# H3AR00.net
KiCad netlist of a schematic drawn in EAGLE
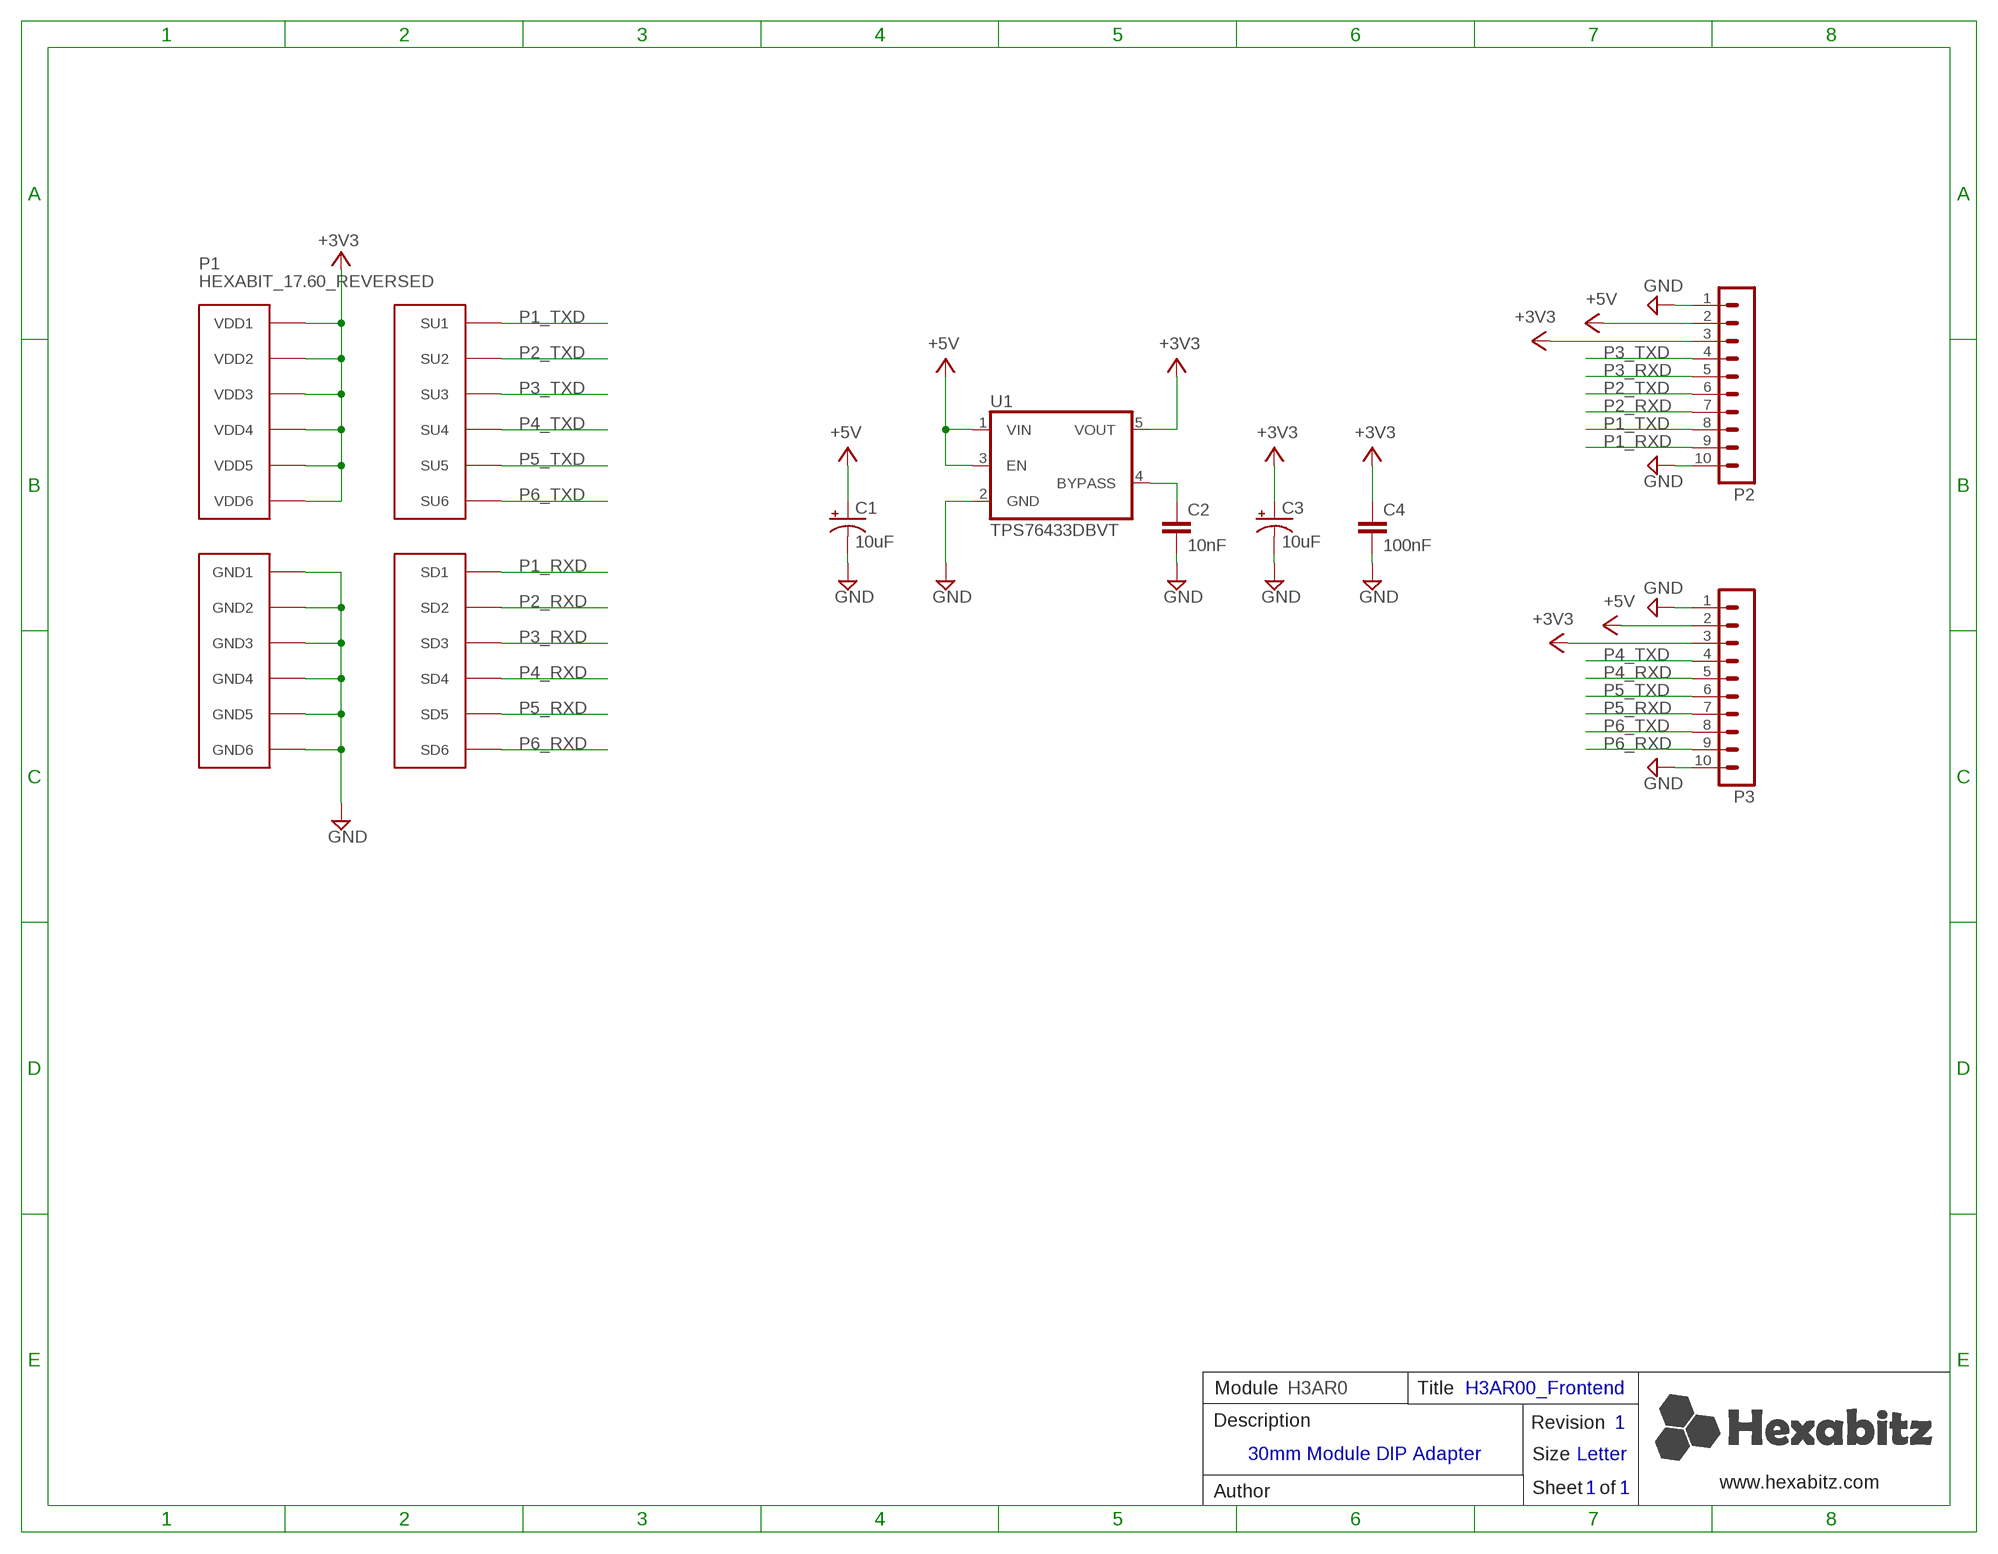
[diagram p0: schematic, sheet 1]

(export (version "E")
  (design (tool "Eeschema 10.0.6"))
  (components
    (comp (ref "C1")
      (value "10uF")
      (footprint "eagle-import:C-1210-POL")
      (fields
        (field (name "CAPACITANCE") "10uF")
        (field (name "MFN") "AVX")
        (field (name "MPN") "TPSB106K016R0500")
        (field (name "OCTOPART_URL") "https://octopart.com/tpsb106k016r0500-avx-1436890?r=sp#")
      )
      (libsource (lib "eagle-import") (part "C-1210-POL"))
    )
    (comp (ref "C2")
      (value "10nF")
      (footprint "eagle-import:C-0603")
      (fields
        (field (name "CAPACITANCE") "10nF")
        (field (name "MFN") "KEMET")
        (field (name "MPN") "C0603C103K5RACTU")
        (field (name "OCTOPART_URL") "https://octopart.com/c0603c103k5ractu-kemet-133094?r=sp&s=R_iPBxLnSmGqhkU2rIMFpg")
        (field (name "TOLERANCE") "10%")
        (field (name "VOLTAGE_RATING") "50V")
      )
      (libsource (lib "eagle-import") (part "C-0603"))
    )
    (comp (ref "C3")
      (value "10uF")
      (footprint "eagle-import:C-1210-POL")
      (fields
        (field (name "CAPACITANCE") "10uF")
        (field (name "MFN") "AVX")
        (field (name "MPN") "TPSB106K016R0500")
        (field (name "OCTOPART_URL") "https://octopart.com/tpsb106k016r0500-avx-1436890?r=sp#")
      )
      (libsource (lib "eagle-import") (part "C-1210-POL"))
    )
    (comp (ref "C4")
      (value "100nF")
      (footprint "eagle-import:C-0603")
      (fields
        (field (name "CAPACITANCE") "100nF")
        (field (name "MFN") "KEMET")
        (field (name "MPN") "C0603C104K8RACTU")
        (field (name "OCTOPART_URL") "https://octopart.com/c0603c104k8ractu-kemet-145075?r=sp&s=9bS9ASSwSEqMCE9KBEQZ0g")
        (field (name "TOLERANCE") "10%")
        (field (name "VOLTAGE_RATING") "10V")
      )
      (libsource (lib "eagle-import") (part "C-0603"))
    )
    (comp (ref "P1")
      (value "HEXABIT_17.60_REVERSED")
      (footprint "eagle-import:HEXABIT_17.60_REVERSED")
      (libsource (lib "eagle-import") (part "HEXABIT_?_REVERSED17.60"))
    )
    (comp (ref "P2")
      (value "MA10-1")
      (footprint "eagle-import:MA10-1")
      (fields (field (name "MPN") "61301011121"))
      (libsource (lib "eagle-import") (part "MA10-1"))
    )
    (comp (ref "P3")
      (value "MA10-1")
      (footprint "eagle-import:MA10-1")
      (fields (field (name "MPN") "61301011121"))
      (libsource (lib "eagle-import") (part "MA10-1"))
    )
    (comp (ref "U1")
      (value "TPS76433DBVT")
      (footprint "eagle-import:SOT25")
      (libsource (lib "eagle-import") (part "TPS764DBVT33"))
    )
  )
  (nets
    (net (code "1") (name "+3V3") (class "Default")
      (node (ref "C3") (pin "1") (pinfunction "+_1") (pintype "passive"))
      (node (ref "C4") (pin "1") (pinfunction "1_1") (pintype "passive"))
      (node (ref "P1") (pin "PAD_PU10") (pinfunction "VDD4_PAD_PU10") (pintype "power_in"))
      (node (ref "P1") (pin "PAD_PU11") (pinfunction "VDD5_PAD_PU11") (pintype "power_in"))
      (node (ref "P1") (pin "PAD_PU12") (pinfunction "VDD6_PAD_PU12") (pintype "power_in"))
      (node (ref "P1") (pin "PAD_PU7") (pinfunction "VDD1_PAD_PU7") (pintype "power_in"))
      (node (ref "P1") (pin "PAD_PU8") (pinfunction "VDD2_PAD_PU8") (pintype "power_in"))
      (node (ref "P1") (pin "PAD_PU9") (pinfunction "VDD3_PAD_PU9") (pintype "power_in"))
      (node (ref "P2") (pin "3") (pinfunction "3_3") (pintype "passive"))
      (node (ref "P3") (pin "3") (pinfunction "3_3") (pintype "passive"))
      (node (ref "U1") (pin "5") (pinfunction "VOUT_5") (pintype "passive"))
    )
    (net (code "2") (name "+5V") (class "Default")
      (node (ref "C1") (pin "1") (pinfunction "+_1") (pintype "passive"))
      (node (ref "P2") (pin "2") (pinfunction "2_2") (pintype "passive"))
      (node (ref "P3") (pin "2") (pinfunction "2_2") (pintype "passive"))
      (node (ref "U1") (pin "1") (pinfunction "VIN_1") (pintype "input"))
      (node (ref "U1") (pin "3") (pinfunction "EN_3") (pintype "input"))
    )
    (net (code "3") (name "/P1_RXD") (class "Default")
      (node (ref "P1") (pin "PAD_PD1") (pinfunction "SD1_PAD_PD1") (pintype "bidirectional"))
      (node (ref "P2") (pin "9") (pinfunction "9_9") (pintype "passive"))
    )
    (net (code "4") (name "/P1_TXD") (class "Default")
      (node (ref "P1") (pin "PAD_PU1") (pinfunction "SU1_PAD_PU1") (pintype "bidirectional"))
      (node (ref "P2") (pin "8") (pinfunction "8_8") (pintype "passive"))
    )
    (net (code "5") (name "/P2_RXD") (class "Default")
      (node (ref "P1") (pin "PAD_PD2") (pinfunction "SD2_PAD_PD2") (pintype "bidirectional"))
      (node (ref "P2") (pin "7") (pinfunction "7_7") (pintype "passive"))
    )
    (net (code "6") (name "/P2_TXD") (class "Default")
      (node (ref "P1") (pin "PAD_PU2") (pinfunction "SU2_PAD_PU2") (pintype "bidirectional"))
      (node (ref "P2") (pin "6") (pinfunction "6_6") (pintype "passive"))
    )
    (net (code "7") (name "/P3_RXD") (class "Default")
      (node (ref "P1") (pin "PAD_PD3") (pinfunction "SD3_PAD_PD3") (pintype "bidirectional"))
      (node (ref "P2") (pin "5") (pinfunction "5_5") (pintype "passive"))
    )
    (net (code "8") (name "/P3_TXD") (class "Default")
      (node (ref "P1") (pin "PAD_PU3") (pinfunction "SU3_PAD_PU3") (pintype "bidirectional"))
      (node (ref "P2") (pin "4") (pinfunction "4_4") (pintype "passive"))
    )
    (net (code "9") (name "/P4_RXD") (class "Default")
      (node (ref "P1") (pin "PAD_PD4") (pinfunction "SD4_PAD_PD4") (pintype "bidirectional"))
      (node (ref "P3") (pin "5") (pinfunction "5_5") (pintype "passive"))
    )
    (net (code "10") (name "/P4_TXD") (class "Default")
      (node (ref "P1") (pin "PAD_PU4") (pinfunction "SU4_PAD_PU4") (pintype "bidirectional"))
      (node (ref "P3") (pin "4") (pinfunction "4_4") (pintype "passive"))
    )
    (net (code "11") (name "/P5_RXD") (class "Default")
      (node (ref "P1") (pin "PAD_PD5") (pinfunction "SD5_PAD_PD5") (pintype "bidirectional"))
      (node (ref "P3") (pin "7") (pinfunction "7_7") (pintype "passive"))
    )
    (net (code "12") (name "/P5_TXD") (class "Default")
      (node (ref "P1") (pin "PAD_PU5") (pinfunction "SU5_PAD_PU5") (pintype "bidirectional"))
      (node (ref "P3") (pin "6") (pinfunction "6_6") (pintype "passive"))
    )
    (net (code "13") (name "/P6_RXD") (class "Default")
      (node (ref "P1") (pin "PAD_PD6") (pinfunction "SD6_PAD_PD6") (pintype "bidirectional"))
      (node (ref "P3") (pin "9") (pinfunction "9_9") (pintype "passive"))
    )
    (net (code "14") (name "/P6_TXD") (class "Default")
      (node (ref "P1") (pin "PAD_PU6") (pinfunction "SU6_PAD_PU6") (pintype "bidirectional"))
      (node (ref "P3") (pin "8") (pinfunction "8_8") (pintype "passive"))
    )
    (net (code "15") (name "GND") (class "Default")
      (node (ref "C1") (pin "2") (pinfunction "-_2") (pintype "passive"))
      (node (ref "C2") (pin "2") (pinfunction "2_2") (pintype "passive"))
      (node (ref "C3") (pin "2") (pinfunction "-_2") (pintype "passive"))
      (node (ref "C4") (pin "2") (pinfunction "2_2") (pintype "passive"))
      (node (ref "P1") (pin "PAD_PD10") (pinfunction "GND4_PAD_PD10") (pintype "power_in"))
      (node (ref "P1") (pin "PAD_PD11") (pinfunction "GND5_PAD_PD11") (pintype "power_in"))
      (node (ref "P1") (pin "PAD_PD12") (pinfunction "GND6_PAD_PD12") (pintype "power_in"))
      (node (ref "P1") (pin "PAD_PD7") (pinfunction "GND1_PAD_PD7") (pintype "power_in"))
      (node (ref "P1") (pin "PAD_PD8") (pinfunction "GND2_PAD_PD8") (pintype "power_in"))
      (node (ref "P1") (pin "PAD_PD9") (pinfunction "GND3_PAD_PD9") (pintype "power_in"))
      (node (ref "P2") (pin "1") (pinfunction "1_1") (pintype "passive"))
      (node (ref "P2") (pin "10") (pinfunction "10_10") (pintype "passive"))
      (node (ref "P3") (pin "1") (pinfunction "1_1") (pintype "passive"))
      (node (ref "P3") (pin "10") (pinfunction "10_10") (pintype "passive"))
      (node (ref "U1") (pin "2") (pinfunction "GND_2") (pintype "passive"))
    )
    (net (code "16") (name "Net-(U1-BYPASS)") (class "Default")
      (node (ref "C2") (pin "1") (pinfunction "1_1") (pintype "passive"))
      (node (ref "U1") (pin "4") (pinfunction "BYPASS_4") (pintype "input"))
    )
  )
)
